# LEDS_Schematic.net
KiCad netlist of a schematic drawn in Altium Designer
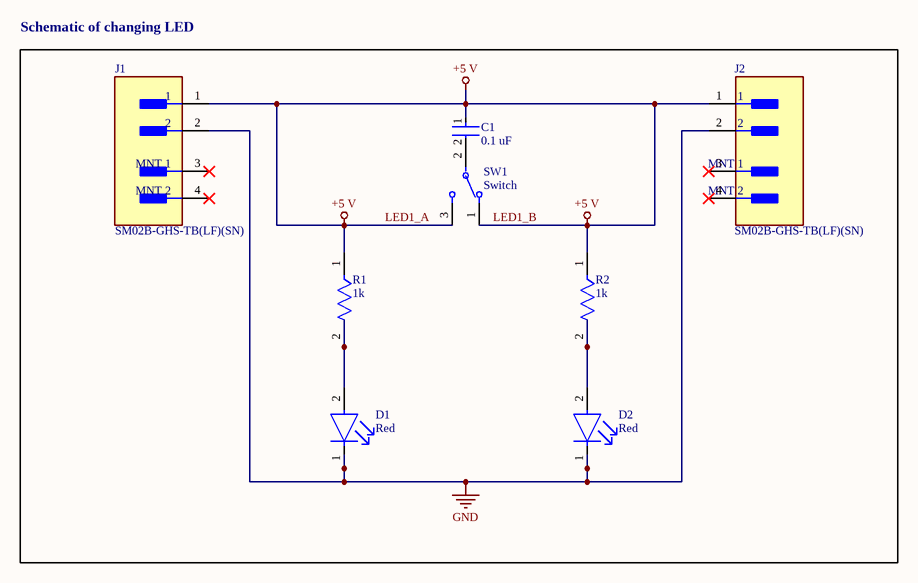
[diagram p0: LEDS! Schematic.SchDoc]

(export (version "E")
  (design (tool "Eeschema 10.0.6"))
  (components
    (comp (ref "C1")
      (value "0.1 uF")
      (footprint "FP-GRM155-0_05-IPC_C")
      (description "Chip Multilayer Ceramic Capacitors for General Purpose, 0402, 0.10uF, X7R, 15%, 10%, 25V")
      (fields (field (name "TOLERANCE") "10%"))
      (libsource (lib "Altium Content Vault") (part "02cd4be3c70576c341d710602a673aa"))
    )
    (comp (ref "D1")
      (value "Red")
      (footprint "FP-LTST-C230EKT-MFG")
      (description "LED RED CLEAR CHIP SMD")
      (libsource (lib "Altium Content Vault") (part "8706943c75ba83719d021d2fdc84c58"))
    )
    (comp (ref "D2")
      (value "Red")
      (footprint "FP-LTST-C230EKT-MFG")
      (description "LED RED CLEAR CHIP SMD")
      (libsource (lib "Altium Content Vault") (part "8706943c75ba83719d021d2fdc84c58"))
    )
    (comp (ref "J1")
      (value "SM02B-GHS-TB(LF)(SN)")
      (footprint "FP-SM02B-GHS-TB_LF_SN-MFG")
      (description "CONN HEADER SMD R/A 2POS 1.25MM")
      (libsource (lib "") (part "56ec3178a87b3978bdc1b3682cd516a_1"))
    )
    (comp (ref "J2")
      (value "SM02B-GHS-TB(LF)(SN)")
      (footprint "FP-SM02B-GHS-TB_LF_SN-MFG")
      (description "CONN HEADER SMD R/A 2POS 1.25MM")
      (libsource (lib "Altium Content Vault") (part "56ec3178a87b3978bdc1b3682cd516a"))
    )
    (comp (ref "R1")
      (value "1k")
      (footprint "FP-RN73R1J-IPC_A")
      (description "3kΩ ±1% 0.1W, 1/10W Chip Resistor 0603 (1608 Metric) Moisture Resistant Thin Film")
      (libsource (lib "Altium Content Vault") (part "1029c3af85768c4190bb7ad29bc67b5"))
    )
    (comp (ref "R2")
      (value "1k")
      (footprint "FP-RN73R1J-IPC_A")
      (description "3kΩ ±1% 0.1W, 1/10W Chip Resistor 0603 (1608 Metric) Moisture Resistant Thin Film")
      (libsource (lib "Altium Content Vault") (part "1029c3af85768c4190bb7ad29bc67b5"))
    )
    (comp (ref "SW1")
      (value "Switch")
      (footprint "FP-7103SYCQE-MFG")
      (description "SWITCH TOGGLE SPDT 5A 120V")
      (libsource (lib "Altium Content Vault") (part "7fcaa069a19c2acd609832313418d7c"))
    )
  )
  (nets
    (net (code "1") (name "+5 V") (class "Default")
      (node (ref "C1") (pin "1") (pinfunction "1_1") (pintype "passive"))
      (node (ref "J1") (pin "1") (pinfunction "1_1") (pintype "passive"))
      (node (ref "J2") (pin "1") (pinfunction "1_1") (pintype "passive"))
      (node (ref "R1") (pin "1") (pinfunction "1_1") (pintype "passive"))
      (node (ref "R2") (pin "1") (pinfunction "1_1") (pintype "passive"))
      (node (ref "SW1") (pin "1") (pinfunction "1_1") (pintype "passive"))
      (node (ref "SW1") (pin "3") (pinfunction "3_3") (pintype "passive"))
    )
    (net (code "2") (name "GND") (class "Default")
      (node (ref "D1") (pin "1") (pinfunction "C_1") (pintype "passive"))
      (node (ref "D2") (pin "1") (pinfunction "C_1") (pintype "passive"))
      (node (ref "J1") (pin "2") (pinfunction "2_2") (pintype "passive"))
      (node (ref "J2") (pin "2") (pinfunction "2_2") (pintype "passive"))
    )
    (net (code "3") (name "Net-(D1-A)") (class "Default")
      (node (ref "D1") (pin "2") (pinfunction "A_2") (pintype "passive"))
      (node (ref "R1") (pin "2") (pinfunction "2_2") (pintype "passive"))
    )
    (net (code "4") (name "Net-(D2-A)") (class "Default")
      (node (ref "D2") (pin "2") (pinfunction "A_2") (pintype "passive"))
      (node (ref "R2") (pin "2") (pinfunction "2_2") (pintype "passive"))
    )
    (net (code "5") (name "Net-(SW1-COMM)") (class "Default")
      (node (ref "C1") (pin "2") (pinfunction "2_2") (pintype "passive"))
      (node (ref "SW1") (pin "2") (pinfunction "COMM_2") (pintype "passive"))
    )
    (net (code "6") (name "unconnected-(J1-MNT_1-Pad3)") (class "Default")
      (node (ref "J1") (pin "3") (pinfunction "MNT_1_3") (pintype "passive+no_connect"))
    )
    (net (code "7") (name "unconnected-(J1-MNT_2-Pad4)") (class "Default")
      (node (ref "J1") (pin "4") (pinfunction "MNT_2_4") (pintype "passive+no_connect"))
    )
    (net (code "8") (name "unconnected-(J2-MNT_1-Pad3)") (class "Default")
      (node (ref "J2") (pin "3") (pinfunction "MNT_1_3") (pintype "passive+no_connect"))
    )
    (net (code "9") (name "unconnected-(J2-MNT_2-Pad4)") (class "Default")
      (node (ref "J2") (pin "4") (pinfunction "MNT_2_4") (pintype "passive+no_connect"))
    )
  )
)
